# Connector-Sheet.net
KiCad netlist of a schematic drawn in Altium Designer
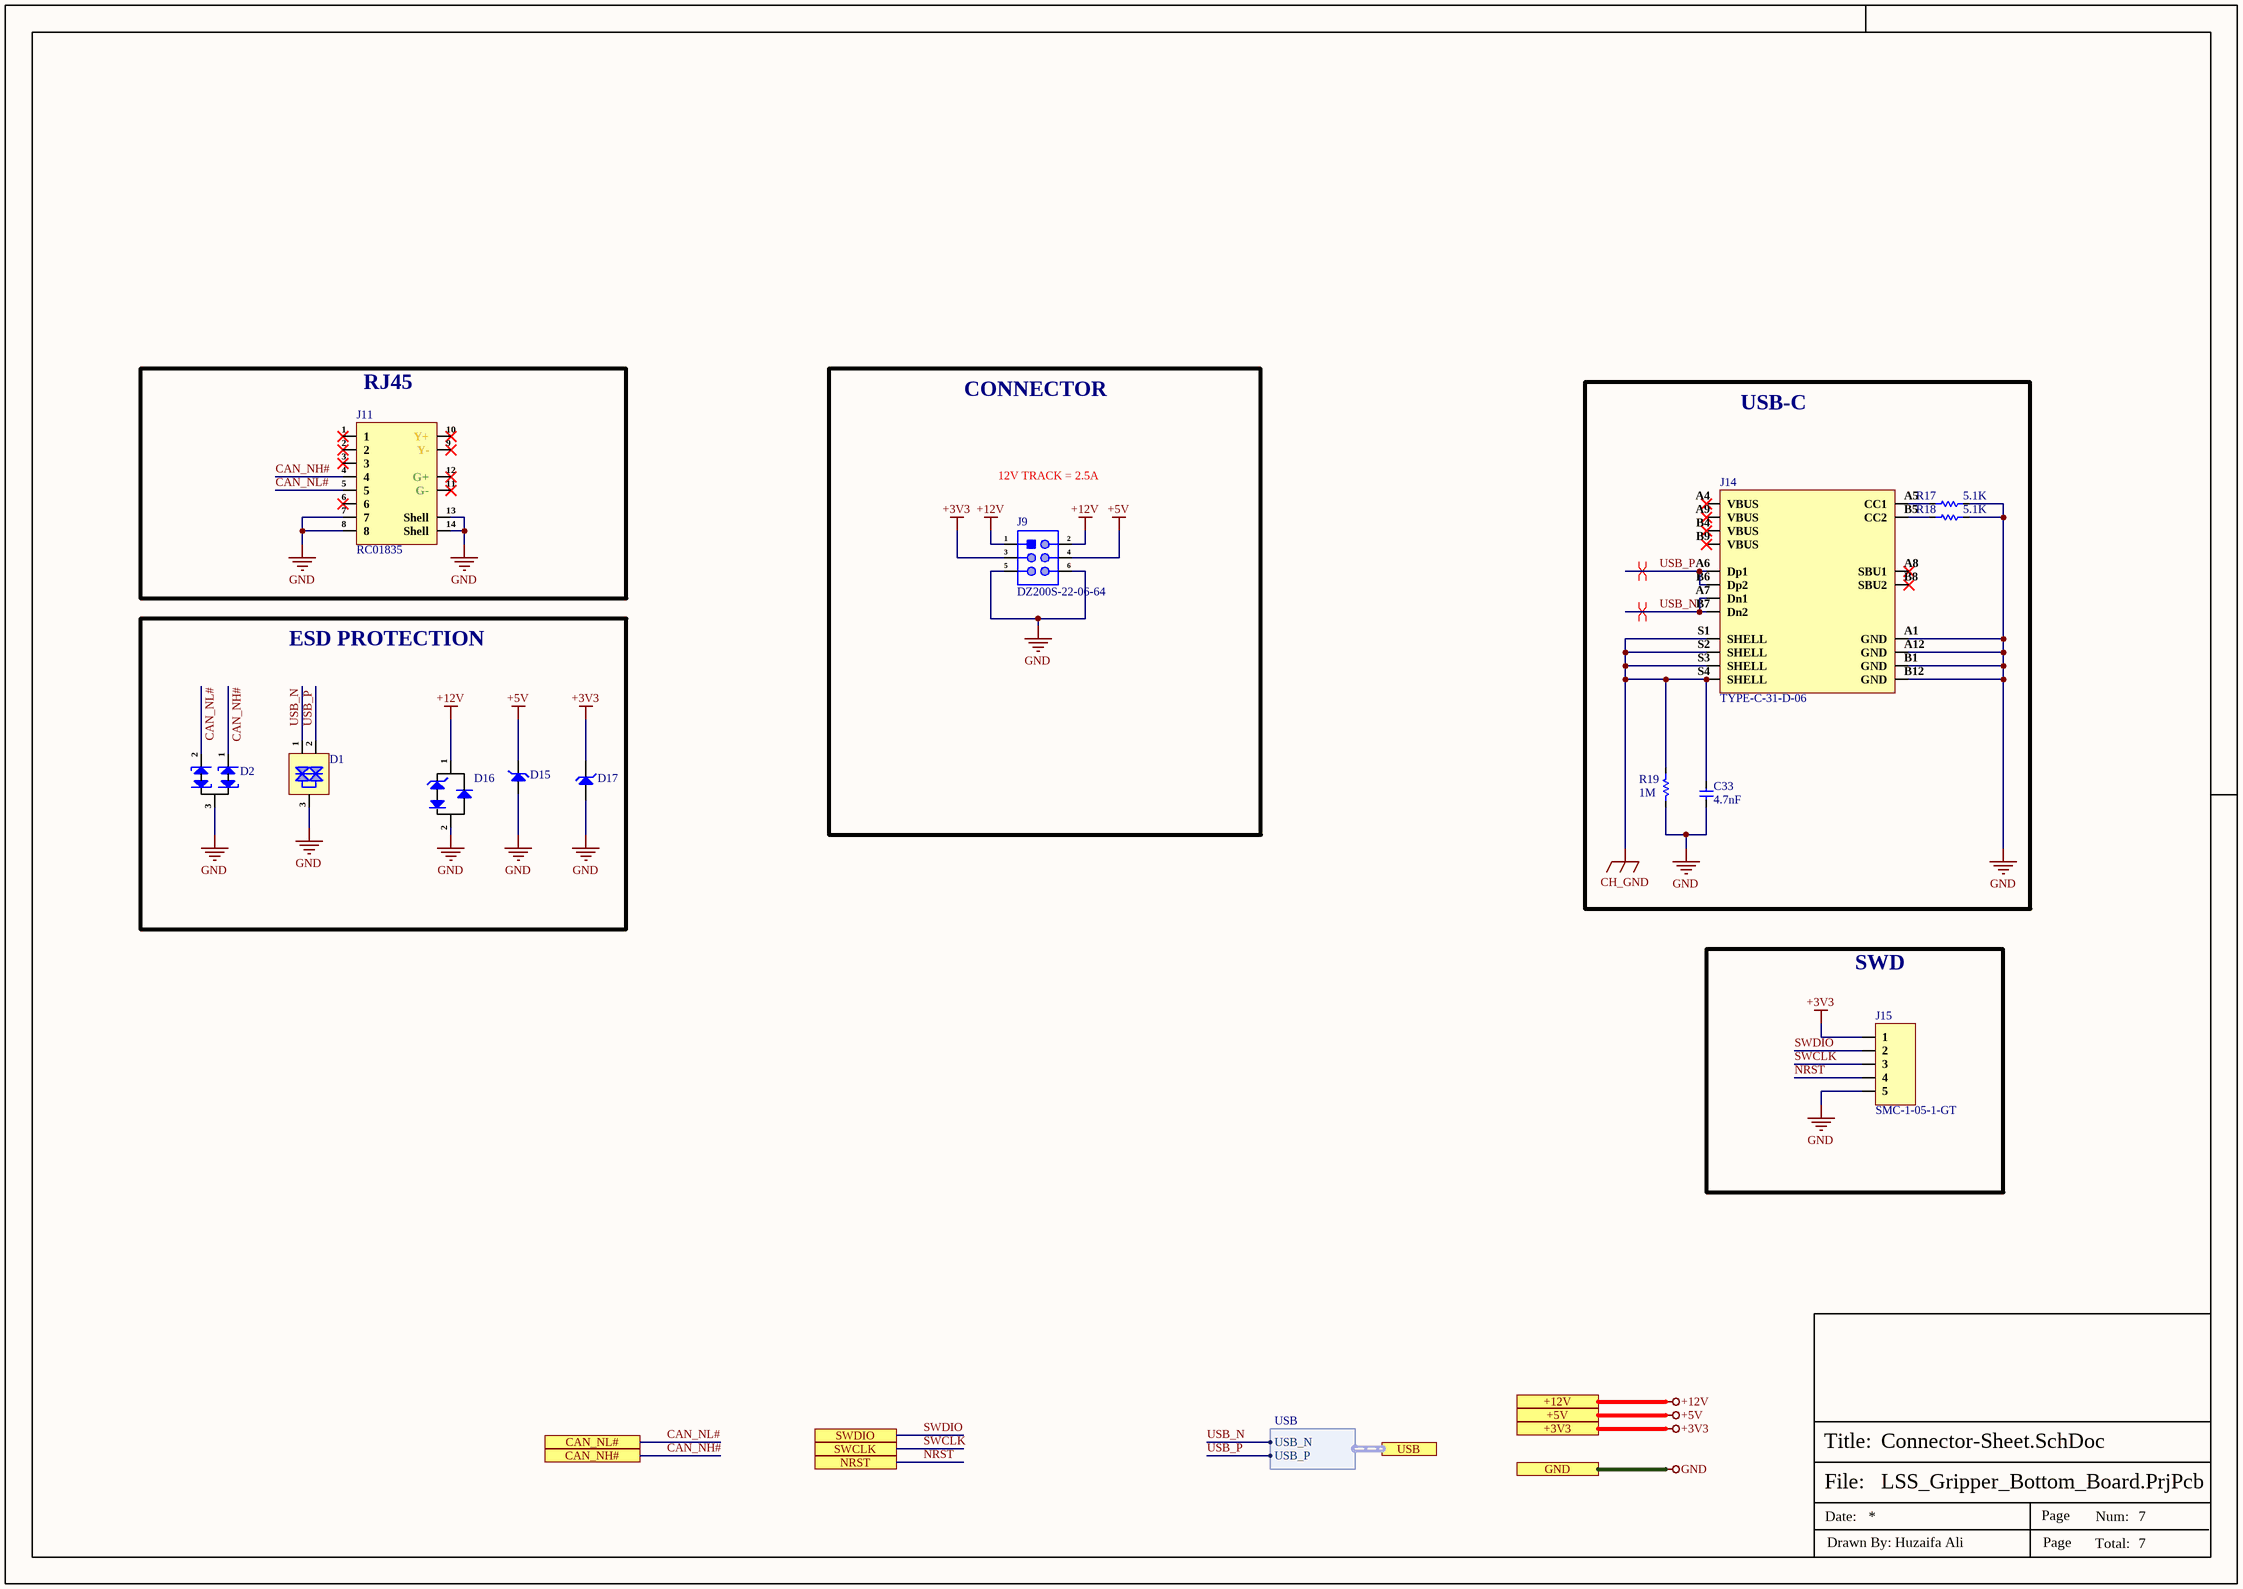
[diagram p0: Connector-Sheet.SchDoc]

(export (version "E")
  (design (tool "Eeschema 10.0.6"))
  (components
    (comp (ref "C33")
      (value "4.7nF")
      (footprint "Cap-1206")
      (description "CAP CER 4700PF 1KV X7R 1206")
      (fields
        (field (name "MANUFACTURER") "Yageo")
        (field (name "MANUFACTURER PART NUMBER") "CC1206KKX7RCBB472")
      )
      (libsource (lib "eSpark Libraries") (part "CC1206KKX7RCBB472"))
    )
    (comp (ref "D1")
      (value "ESD5302F-3/TR")
      (footprint "Sot-23")
      (description "16A 20V 7V 5V@Max Unidirectional SOT-23 TVS ROHS")
      (fields (field (name "MANUFACTURER") "WILLSEMI") (field (name "LCSC PART NUMBER") "C239643"))
      (libsource (lib "eSpark Libraries") (part "ESD5302F-3/TR"))
    )
    (comp (ref "D2")
      (value "PESD2CAN,215")
      (footprint "SOT-23")
      (description "TVS DIODE 24VWM 41VC TO236AB")
      (fields (field (name "MANUFACTURER") "Nexperia") (field (name "LCSC PART NUMBER") "C75176"))
      (libsource (lib "eSpark Libraries") (part "PESD2CAN,215"))
    )
    (comp (ref "D15")
      (value "P6SMB6.8A")
      (footprint "SMB_")
      (fields (field (name "MANUFACTURER") "BORN") (field (name "LCSC PART NUMBER") "C5439947"))
      (libsource (lib "eSpark Libraries") (part "P6SMB6.8A"))
    )
    (comp (ref "D16")
      (value "SD12LC")
      (footprint "SOD-323")
      (description "TVS DIODE 12VWM 28.6VC SOD323")
      (fields (field (name "MANUFACTURER") "Sangdest Microelectronics"))
      (libsource (lib "eSpark Libraries") (part "SD12LC"))
    )
    (comp (ref "D17")
      (value "AZ3003-01G")
      (footprint "SOD-123")
      (description "TVS SURGE PROTECTOR 1-CH 3.3V")
      (fields (field (name "MANUFACTURER") "Amazing"))
      (libsource (lib "eSpark Libraries") (part "AZ3003-01G"))
    )
    (comp (ref "J9")
      (value "DZ200S-22-06-64")
      (footprint "HDR 2x3 Male SMD(2mm Pitch)")
      (description "Brick nogging Square Pins 6P 2mm 双排 2x3P SMD,P=2mm Pin Headers ROHS")
      (fields (field (name "MANUFACTURER") "DEALON") (field (name "LCSC PART NUMBER") "C5160768"))
      (libsource (lib "eSpark Libraries") (part "DZ200S-22-06-64"))
    )
    (comp (ref "J11")
      (value "RC01835")
      (footprint "RC01835")
      (fields (field (name "MANUFACTURER") "RCH") (field (name "LCSC PART NUMBER") "C708648"))
      (libsource (lib "eSpark Libraries") (part "RC01835"))
    )
    (comp (ref "J14")
      (value "TYPE-C-31-D-06")
      (footprint "TYPE-C-31-D-06")
      (description "1 Brick nogging 16 Female -25℃~+85℃ Type-C SMD USB Connectors ROHS")
      (fields
        (field (name "MANUFACTURER") "Korean Hroparts Elec")
        (field (name "LCSC PART NUMBER") "C2689964")
      )
      (libsource (lib "eSpark Libraries") (part "TYPE-C-31-D-06"))
    )
    (comp (ref "J15")
      (value "SMC-1-05-1-GT")
      (footprint "SMC-1-05-1-GT")
      (description "MACHINE PIN SOCKET 5P 2.54MM PIT")
      (fields (field (name "MANUFACTURER") "Adam Equipment") (field (name "LCSC PART NUMBER") "C3320109"))
      (libsource (lib "eSpark Libraries") (part "SMC-1-05-1-GT"))
    )
    (comp (ref "R17")
      (value "5.1K")
      (footprint "Res-0402")
      (description "RES 5.1K OHM 1% 1/16W 0402")
      (fields
        (field (name "MANUFACTURER") "Yageo")
        (field (name "MANUFACTURER PART NUMBER") "RC0402FR-075K1L")
      )
      (libsource (lib "eSpark Libraries") (part "RC0402FR-075K1L"))
    )
    (comp (ref "R18")
      (value "5.1K")
      (footprint "Res-0402")
      (description "RES 5.1K OHM 1% 1/16W 0402")
      (fields
        (field (name "MANUFACTURER") "Yageo")
        (field (name "MANUFACTURER PART NUMBER") "RC0402FR-075K1L")
      )
      (libsource (lib "eSpark Libraries") (part "RC0402FR-075K1L"))
    )
    (comp (ref "R19")
      (value "1M")
      (footprint "Res-0603")
      (description "RES SMD 1M OHM 1% 1/10W 0603")
      (fields
        (field (name "MANUFACTURER") "Yageo")
        (field (name "MANUFACTURER PART NUMBER") "RC0603FR-071ML")
      )
      (libsource (lib "eSpark Libraries") (part "RC0603FR-071ML"))
    )
  )
  (nets
    (net (code "2") (name "+3V3") (class "Default")
      (node (ref "D17") (pin "2") (pinfunction "K_2") (pintype "passive"))
      (node (ref "J15") (pin "1") (pinfunction "1_1") (pintype "passive"))
      (node (ref "J9") (pin "3") (pinfunction "3_3") (pintype "passive"))
    )
    (net (code "3") (name "+5V") (class "Default")
      (node (ref "D15") (pin "2") (pinfunction "C_2") (pintype "passive"))
      (node (ref "J9") (pin "4") (pinfunction "4_4") (pintype "passive"))
    )
    (net (code "4") (name "+12V") (class "Default")
      (node (ref "D16") (pin "1") (pinfunction "K_1") (pintype "passive"))
      (node (ref "J9") (pin "1") (pinfunction "1_1") (pintype "passive"))
      (node (ref "J9") (pin "2") (pinfunction "2_2") (pintype "passive"))
    )
    (net (code "5") (name "/CAN_NH#") (class "Default")
      (node (ref "D2") (pin "1") (pinfunction "K1_1") (pintype "passive"))
      (node (ref "J11") (pin "4") (pinfunction "4_4") (pintype "passive"))
    )
    (net (code "6") (name "/CAN_NL#") (class "Default")
      (node (ref "D2") (pin "2") (pinfunction "K2_2") (pintype "passive"))
      (node (ref "J11") (pin "5") (pinfunction "5_5") (pintype "passive"))
    )
    (net (code "7") (name "/NRST") (class "Default")
      (node (ref "J15") (pin "4") (pinfunction "4_4") (pintype "passive"))
    )
    (net (code "8") (name "/SWCLK") (class "Default")
      (node (ref "J15") (pin "3") (pinfunction "3_3") (pintype "passive"))
    )
    (net (code "9") (name "/SWDIO") (class "Default")
      (node (ref "J15") (pin "2") (pinfunction "2_2") (pintype "passive"))
    )
    (net (code "10") (name "/USB_N") (class "Default")
      (node (ref "D1") (pin "1") (pinfunction "I/O1_1") (pintype "passive"))
      (node (ref "J14") (pin "A7") (pinfunction "Dn1_A7") (pintype "passive"))
      (node (ref "J14") (pin "B7") (pinfunction "Dn2_B7") (pintype "passive"))
    )
    (net (code "11") (name "/USB_P") (class "Default")
      (node (ref "D1") (pin "2") (pinfunction "I/O2_2") (pintype "passive"))
      (node (ref "J14") (pin "A6") (pinfunction "Dp1_A6") (pintype "passive"))
      (node (ref "J14") (pin "B6") (pinfunction "Dp2_B6") (pintype "passive"))
    )
    (net (code "13") (name "CH_GND") (class "Default")
      (node (ref "C33") (pin "1") (pinfunction "1_1") (pintype "passive"))
      (node (ref "J14") (pin "S1") (pinfunction "SHELL_S1") (pintype "passive"))
      (node (ref "J14") (pin "S2") (pinfunction "SHELL_S2") (pintype "passive"))
      (node (ref "J14") (pin "S3") (pinfunction "SHELL_S3") (pintype "passive"))
      (node (ref "J14") (pin "S4") (pinfunction "SHELL_S4") (pintype "passive"))
      (node (ref "R19") (pin "1") (pinfunction "1_1") (pintype "passive"))
    )
    (net (code "14") (name "GND") (class "Default")
      (node (ref "C33") (pin "2") (pinfunction "2_2") (pintype "passive"))
      (node (ref "D1") (pin "3") (pinfunction "GND_3") (pintype "passive"))
      (node (ref "D15") (pin "1") (pinfunction "A_1") (pintype "passive"))
      (node (ref "D16") (pin "2") (pinfunction "A/K_2") (pintype "passive"))
      (node (ref "D17") (pin "1") (pinfunction "A_1") (pintype "passive"))
      (node (ref "D2") (pin "3") (pinfunction "C_K_3") (pintype "passive"))
      (node (ref "J11") (pin "13") (pinfunction "Shell_13") (pintype "passive"))
      (node (ref "J11") (pin "14") (pinfunction "Shell_14") (pintype "passive"))
      (node (ref "J11") (pin "7") (pinfunction "7_7") (pintype "passive"))
      (node (ref "J11") (pin "8") (pinfunction "8_8") (pintype "passive"))
      (node (ref "J14") (pin "A1") (pinfunction "GND_A1") (pintype "power_in"))
      (node (ref "J14") (pin "A12") (pinfunction "GND_A12") (pintype "power_in"))
      (node (ref "J14") (pin "B1") (pinfunction "GND_B1") (pintype "power_in"))
      (node (ref "J14") (pin "B12") (pinfunction "GND_B12") (pintype "power_in"))
      (node (ref "J15") (pin "5") (pinfunction "5_5") (pintype "passive"))
      (node (ref "J9") (pin "5") (pinfunction "5_5") (pintype "passive"))
      (node (ref "J9") (pin "6") (pinfunction "6_6") (pintype "passive"))
      (node (ref "R17") (pin "2") (pinfunction "2_2") (pintype "passive"))
      (node (ref "R18") (pin "2") (pinfunction "2_2") (pintype "passive"))
      (node (ref "R19") (pin "2") (pinfunction "2_2") (pintype "passive"))
    )
    (net (code "15") (name "Net-(J14-CC1)") (class "Default")
      (node (ref "J14") (pin "A5") (pinfunction "CC1_A5") (pintype "passive"))
      (node (ref "R17") (pin "1") (pinfunction "1_1") (pintype "passive"))
    )
    (net (code "16") (name "Net-(J14-CC2)") (class "Default")
      (node (ref "J14") (pin "B5") (pinfunction "CC2_B5") (pintype "passive"))
      (node (ref "R18") (pin "1") (pinfunction "1_1") (pintype "passive"))
    )
    (net (code "17") (name "unconnected-(J11-G+-Pad12)") (class "Default")
      (node (ref "J11") (pin "12") (pinfunction "G+_12") (pintype "passive+no_connect"))
    )
    (net (code "18") (name "unconnected-(J11-G--Pad11)") (class "Default")
      (node (ref "J11") (pin "11") (pinfunction "G-_11") (pintype "passive+no_connect"))
    )
    (net (code "19") (name "unconnected-(J11-Pad1)") (class "Default")
      (node (ref "J11") (pin "1") (pinfunction "1_1") (pintype "passive+no_connect"))
    )
    (net (code "20") (name "unconnected-(J11-Pad2)") (class "Default")
      (node (ref "J11") (pin "2") (pinfunction "2_2") (pintype "passive+no_connect"))
    )
    (net (code "21") (name "unconnected-(J11-Pad3)") (class "Default")
      (node (ref "J11") (pin "3") (pinfunction "3_3") (pintype "passive+no_connect"))
    )
    (net (code "22") (name "unconnected-(J11-Pad6)") (class "Default")
      (node (ref "J11") (pin "6") (pinfunction "6_6") (pintype "passive+no_connect"))
    )
    (net (code "23") (name "unconnected-(J11-Y+-Pad10)") (class "Default")
      (node (ref "J11") (pin "10") (pinfunction "Y+_10") (pintype "passive+no_connect"))
    )
    (net (code "24") (name "unconnected-(J11-Y--Pad9)") (class "Default")
      (node (ref "J11") (pin "9") (pinfunction "Y-_9") (pintype "passive+no_connect"))
    )
    (net (code "25") (name "unconnected-(J14-SBU1-PadA8)") (class "Default")
      (node (ref "J14") (pin "A8") (pinfunction "SBU1_A8") (pintype "passive+no_connect"))
    )
    (net (code "26") (name "unconnected-(J14-SBU2-PadB8)") (class "Default")
      (node (ref "J14") (pin "B8") (pinfunction "SBU2_B8") (pintype "passive+no_connect"))
    )
    (net (code "27") (name "unconnected-(J14-VBUS-PadA4)") (class "Default")
      (node (ref "J14") (pin "A4") (pinfunction "VBUS_A4") (pintype "power_in+no_connect"))
    )
    (net (code "28") (name "unconnected-(J14-VBUS-PadA9)") (class "Default")
      (node (ref "J14") (pin "A9") (pinfunction "VBUS_A9") (pintype "power_in+no_connect"))
    )
    (net (code "29") (name "unconnected-(J14-VBUS-PadB4)") (class "Default")
      (node (ref "J14") (pin "B4") (pinfunction "VBUS_B4") (pintype "power_in+no_connect"))
    )
    (net (code "30") (name "unconnected-(J14-VBUS-PadB9)") (class "Default")
      (node (ref "J14") (pin "B9") (pinfunction "VBUS_B9") (pintype "power_in+no_connect"))
    )
  )
)
